# MainBoard_Schematic.net
KiCad netlist of a schematic drawn in Altium Designer
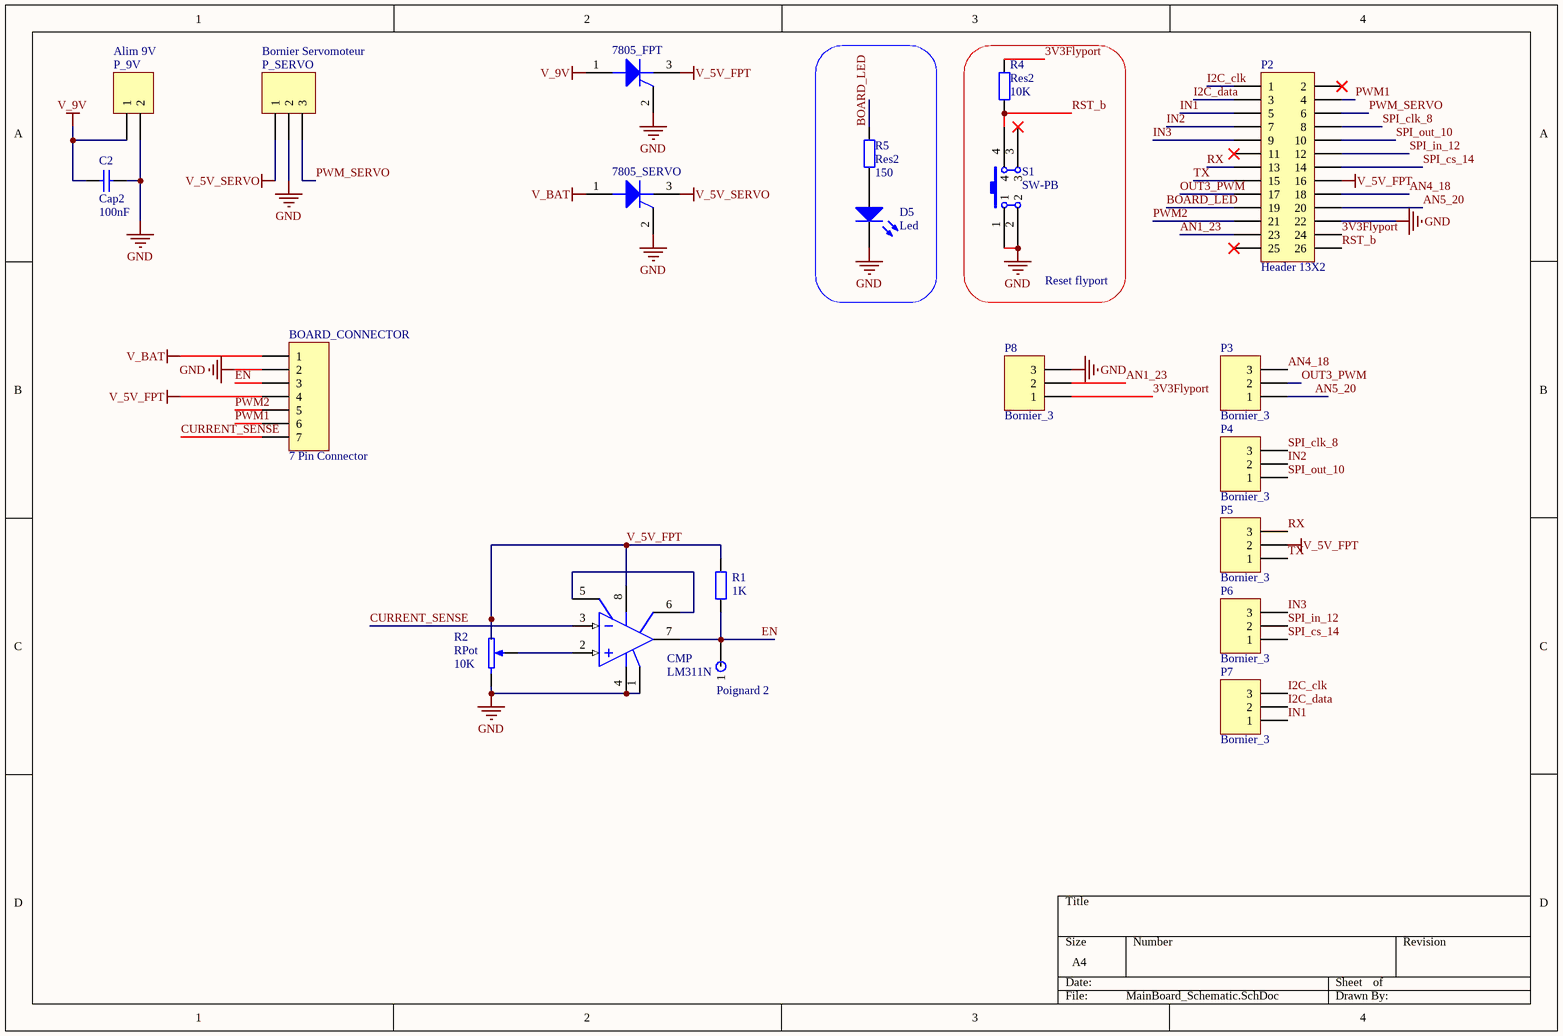
[diagram p0: MainBoard_Schematic.SchDoc]

(export (version "E")
  (design (tool "Eeschema 10.0.6"))
  (components
    (comp (ref "7805_FPT")
      (value "SCR")
      (footprint "TO-220-AB")
      (description "Silicon Controlled Rectifier")
      (fields (field (name "PUBLISHER") "Altium Limited"))
      (libsource (lib "Miscellaneous Devices") (part "SCR"))
    )
    (comp (ref "7805_SERVO")
      (value "SCR")
      (footprint "TO-220-AB")
      (description "Silicon Controlled Rectifier")
      (fields (field (name "PUBLISHER") "Altium Limited"))
      (libsource (lib "Miscellaneous Devices") (part "SCR"))
    )
    (comp (ref "BOARD_CONNECTOR")
      (value "7 Pin Connector")
      (footprint "HDR1X7")
      (description "Header, 7-Pin")
      (fields (field (name "PUBLISHER") "Altium Limited"))
      (libsource (lib "Miscellaneous Connectors") (part "Header 7"))
    )
    (comp (ref "C2")
      (value "Cap2")
      (footprint "CAPA2")
      (description "Capacitor")
      (fields (field (name "ALTIUM_VALUE") "100nF") (field (name "PUBLISHER") "Altium Limited"))
      (libsource (lib "LIBRAIRIE_INTEGREE_PHELMA1") (part "Cap2"))
    )
    (comp (ref "CMP")
      (value "LM311N")
      (footprint "LIBRAIRIE_INTEGREE_PHELMA1:DIP8")
      (description "Voltage Comparator")
      (fields (field (name "PUBLISHER") "Altium Limited"))
      (libsource (lib "LIBRAIRIE_INTEGREE_PHELMA1") (part "LM311N"))
    )
    (comp (ref "D5")
      (value "Led")
      (footprint "LED")
      (description "LED")
      (fields (field (name "PUBLISHER") "Altium Limited"))
      (libsource (lib "LIBRAIRIE_INTEGREE_PHELMA1") (part "Led"))
    )
    (comp (ref "P2")
      (value "Header 13X2")
      (footprint "HDR2X13")
      (description "Header, 13-Pin, Dual row")
      (fields (field (name "PUBLISHER") "Altium Limited"))
      (libsource (lib "Miscellaneous Connectors") (part "Header 13X2"))
    )
    (comp (ref "P3")
      (value "Bornier_3")
      (footprint "Bornier_3")
      (description "Header, 3-Pin")
      (fields (field (name "PUBLISHER") "Altium Limited"))
      (libsource (lib "") (part "Bornier_3_1"))
    )
    (comp (ref "P4")
      (value "Bornier_3")
      (footprint "Bornier_3")
      (description "Header, 3-Pin")
      (fields (field (name "PUBLISHER") "Altium Limited"))
      (libsource (lib "") (part "Bornier_3_1"))
    )
    (comp (ref "P5")
      (value "Bornier_3")
      (footprint "Bornier_3")
      (description "Header, 3-Pin")
      (fields (field (name "PUBLISHER") "Altium Limited"))
      (libsource (lib "") (part "Bornier_3_1"))
    )
    (comp (ref "P6")
      (value "Bornier_3")
      (footprint "Bornier_3")
      (description "Header, 3-Pin")
      (fields (field (name "PUBLISHER") "Altium Limited"))
      (libsource (lib "") (part "Bornier_3_1"))
    )
    (comp (ref "P7")
      (value "Bornier_3")
      (footprint "Bornier_3")
      (description "Header, 3-Pin")
      (fields (field (name "PUBLISHER") "Altium Limited"))
      (libsource (lib "") (part "Bornier_3_1"))
    )
    (comp (ref "P8")
      (value "Bornier_3")
      (footprint "Bornier_3")
      (description "Header, 3-Pin")
      (fields (field (name "PUBLISHER") "Altium Limited"))
      (libsource (lib "") (part "Bornier_3_1"))
    )
    (comp (ref "Poignard 2")
      (value "Poignard")
      (footprint "Poignard")
      (fields (field (name "PUBLISHER") "Altium Limited"))
      (libsource (lib "INTEGRATED_LIBRARY1_CONNECTEURS") (part "Poignard"))
    )
    (comp (ref "P_9V")
      (value "Alim 9V")
      (footprint "Bornier_2")
      (description "Header, 2-Pin")
      (fields (field (name "PUBLISHER") "Altium Limited"))
      (libsource (lib "INTEGRATED_LIBRARY1_CONNECTEURS") (part "Bornier_2"))
    )
    (comp (ref "P_SERVO")
      (value "Bornier Servomoteur")
      (footprint "Bornier_3")
      (description "Header, 3-Pin")
      (fields (field (name "PUBLISHER") "Altium Limited"))
      (libsource (lib "INTEGRATED_LIBRARY1_CONNECTEURS") (part "Bornier_3"))
    )
    (comp (ref "R1")
      (value "1K")
      (footprint "res5_1/4W")
      (description "Resistor")
      (fields (field (name "Comment") "Res2") (field (name "PUBLISHER") "Altium Limited"))
      (libsource (lib "") (part "Res2_1"))
    )
    (comp (ref "R2")
      (value "RPot")
      (footprint "AJUSTABLE")
      (description "Potentiometer")
      (fields (field (name "ALTIUM_VALUE") "10K") (field (name "PUBLISHER") "Altium Limited"))
      (libsource (lib "LIBRAIRIE_INTEGREE_PHELMA1") (part "RPot"))
    )
    (comp (ref "R4")
      (value "Res2")
      (footprint "res5_1/4W")
      (description "Resistor")
      (fields (field (name "ALTIUM_VALUE") "10K") (field (name "PUBLISHER") "Altium Limited"))
      (libsource (lib "LIBRAIRIE_INTEGREE_PHELMA1") (part "Res2"))
    )
    (comp (ref "R5")
      (value "Res2")
      (footprint "res5_1/4W")
      (description "Resistor")
      (fields (field (name "ALTIUM_VALUE") "150") (field (name "PUBLISHER") "Altium Limited"))
      (libsource (lib "LIBRAIRIE_INTEGREE_PHELMA1") (part "Res2"))
    )
    (comp (ref "S1")
      (value "SW-PB")
      (footprint "SW_BP")
      (description "Switch")
      (fields (field (name "PUBLISHER") "Altium Limited"))
      (libsource (lib "INTEGRATED_LIBRARY1_CONNECTEURS") (part "SW-PB"))
    )
  )
  (nets
    (net (code "1") (name "/3V3Flyport") (class "Default")
      (node (ref "P2") (pin "24") (pinfunction "24_24") (pintype "passive"))
      (node (ref "P8") (pin "1") (pinfunction "1_1") (pintype "passive"))
      (node (ref "R4") (pin "1") (pinfunction "1_1") (pintype "passive"))
    )
    (net (code "2") (name "/AN1_23") (class "Default")
      (node (ref "P2") (pin "23") (pinfunction "23_23") (pintype "passive"))
      (node (ref "P8") (pin "2") (pinfunction "2_2") (pintype "passive"))
    )
    (net (code "3") (name "/AN4_18") (class "Default")
      (node (ref "P2") (pin "18") (pinfunction "18_18") (pintype "passive"))
      (node (ref "P3") (pin "3") (pinfunction "3_3") (pintype "passive"))
    )
    (net (code "4") (name "/AN5_20") (class "Default")
      (node (ref "P2") (pin "20") (pinfunction "20_20") (pintype "passive"))
      (node (ref "P3") (pin "1") (pinfunction "1_1") (pintype "passive"))
    )
    (net (code "5") (name "/BOARD_LED") (class "Default")
      (node (ref "P2") (pin "19") (pinfunction "19_19") (pintype "passive"))
      (node (ref "R5") (pin "1") (pinfunction "1_1") (pintype "passive"))
    )
    (net (code "6") (name "/CURRENT_SENSE") (class "Default")
      (node (ref "BOARD_CONNECTOR") (pin "7") (pinfunction "7_7") (pintype "passive"))
      (node (ref "CMP") (pin "3") (pinfunction "IN-_3") (pintype "input"))
    )
    (net (code "7") (name "/EN") (class "Default")
      (node (ref "BOARD_CONNECTOR") (pin "3") (pinfunction "3_3") (pintype "passive"))
      (node (ref "CMP") (pin "7") (pinfunction "OUT_7") (pintype "open_collector"))
      (node (ref "Poignard 2") (pin "1") (pinfunction "1_1") (pintype "passive"))
      (node (ref "R1") (pin "1") (pinfunction "1_1") (pintype "passive"))
    )
    (net (code "8") (name "/I2C_clk") (class "Default")
      (node (ref "P2") (pin "1") (pinfunction "1_1") (pintype "passive"))
      (node (ref "P7") (pin "3") (pinfunction "3_3") (pintype "passive"))
    )
    (net (code "9") (name "/I2C_data") (class "Default")
      (node (ref "P2") (pin "3") (pinfunction "3_3") (pintype "passive"))
      (node (ref "P7") (pin "2") (pinfunction "2_2") (pintype "passive"))
    )
    (net (code "10") (name "/IN1") (class "Default")
      (node (ref "P2") (pin "5") (pinfunction "5_5") (pintype "passive"))
      (node (ref "P7") (pin "1") (pinfunction "1_1") (pintype "passive"))
    )
    (net (code "11") (name "/IN2") (class "Default")
      (node (ref "P2") (pin "7") (pinfunction "7_7") (pintype "passive"))
      (node (ref "P4") (pin "2") (pinfunction "2_2") (pintype "passive"))
    )
    (net (code "12") (name "/IN3") (class "Default")
      (node (ref "P2") (pin "9") (pinfunction "9_9") (pintype "passive"))
      (node (ref "P6") (pin "3") (pinfunction "3_3") (pintype "passive"))
    )
    (net (code "13") (name "/OUT3_PWM") (class "Default")
      (node (ref "P2") (pin "17") (pinfunction "17_17") (pintype "passive"))
      (node (ref "P3") (pin "2") (pinfunction "2_2") (pintype "passive"))
    )
    (net (code "14") (name "/PWM1") (class "Default")
      (node (ref "BOARD_CONNECTOR") (pin "6") (pinfunction "6_6") (pintype "passive"))
      (node (ref "P2") (pin "4") (pinfunction "4_4") (pintype "passive"))
    )
    (net (code "15") (name "/PWM2") (class "Default")
      (node (ref "BOARD_CONNECTOR") (pin "5") (pinfunction "5_5") (pintype "passive"))
      (node (ref "P2") (pin "21") (pinfunction "21_21") (pintype "passive"))
    )
    (net (code "16") (name "/PWM_SERVO") (class "Default")
      (node (ref "P2") (pin "6") (pinfunction "6_6") (pintype "passive"))
      (node (ref "P_SERVO") (pin "3") (pinfunction "3_3") (pintype "passive"))
    )
    (net (code "17") (name "/RST_b") (class "Default")
      (node (ref "P2") (pin "26") (pinfunction "26_26") (pintype "passive"))
      (node (ref "R4") (pin "2") (pinfunction "2_2") (pintype "passive"))
      (node (ref "S1") (pin "4") (pinfunction "4_4") (pintype "passive"))
    )
    (net (code "18") (name "/RX") (class "Default")
      (node (ref "P2") (pin "13") (pinfunction "13_13") (pintype "passive"))
      (node (ref "P5") (pin "3") (pinfunction "3_3") (pintype "passive"))
    )
    (net (code "19") (name "/SPI_clk_8") (class "Default")
      (node (ref "P2") (pin "8") (pinfunction "8_8") (pintype "passive"))
      (node (ref "P4") (pin "3") (pinfunction "3_3") (pintype "passive"))
    )
    (net (code "20") (name "/SPI_cs_14") (class "Default")
      (node (ref "P2") (pin "14") (pinfunction "14_14") (pintype "passive"))
      (node (ref "P6") (pin "1") (pinfunction "1_1") (pintype "passive"))
    )
    (net (code "21") (name "/SPI_in_12") (class "Default")
      (node (ref "P2") (pin "12") (pinfunction "12_12") (pintype "passive"))
      (node (ref "P6") (pin "2") (pinfunction "2_2") (pintype "passive"))
    )
    (net (code "22") (name "/SPI_out_10") (class "Default")
      (node (ref "P2") (pin "10") (pinfunction "10_10") (pintype "passive"))
      (node (ref "P4") (pin "1") (pinfunction "1_1") (pintype "passive"))
    )
    (net (code "23") (name "/TX") (class "Default")
      (node (ref "P2") (pin "15") (pinfunction "15_15") (pintype "passive"))
      (node (ref "P5") (pin "1") (pinfunction "1_1") (pintype "passive"))
    )
    (net (code "24") (name "GND") (class "Default")
      (node (ref "7805_FPT") (pin "2") (pinfunction "GND_2") (pintype "power_in"))
      (node (ref "7805_SERVO") (pin "2") (pinfunction "GND_2") (pintype "power_in"))
      (node (ref "BOARD_CONNECTOR") (pin "2") (pinfunction "2_2") (pintype "passive"))
      (node (ref "C2") (pin "2") (pinfunction "2_2") (pintype "passive"))
      (node (ref "CMP") (pin "1") (pinfunction "GND_1") (pintype "power_in"))
      (node (ref "CMP") (pin "4") (pinfunction "V-_(CASE)_4") (pintype "power_in"))
      (node (ref "D5") (pin "2") (pinfunction "K_2") (pintype "passive"))
      (node (ref "P2") (pin "22") (pinfunction "22_22") (pintype "passive"))
      (node (ref "P8") (pin "3") (pinfunction "3_3") (pintype "passive"))
      (node (ref "P_9V") (pin "2") (pinfunction "2_2") (pintype "passive"))
      (node (ref "P_SERVO") (pin "2") (pinfunction "2_2") (pintype "passive"))
      (node (ref "R2") (pin "3") (pinfunction "TOP_3") (pintype "passive"))
      (node (ref "S1") (pin "1") (pinfunction "1_1") (pintype "passive"))
      (node (ref "S1") (pin "2") (pinfunction "2_2") (pintype "passive"))
    )
    (net (code "25") (name "Net-(CMP-BAL)") (class "Default")
      (node (ref "CMP") (pin "5") (pinfunction "BAL_5") (pintype "passive"))
      (node (ref "CMP") (pin "6") (pinfunction "BAL/STB_6") (pintype "passive"))
    )
    (net (code "26") (name "Net-(CMP-IN+)") (class "Default")
      (node (ref "CMP") (pin "2") (pinfunction "IN+_2") (pintype "input"))
      (node (ref "R2") (pin "2") (pinfunction "TAP_2") (pintype "passive"))
    )
    (net (code "27") (name "Net-(D5-A)") (class "Default")
      (node (ref "D5") (pin "1") (pinfunction "A_1") (pintype "passive"))
      (node (ref "R5") (pin "2") (pinfunction "2_2") (pintype "passive"))
    )
    (net (code "28") (name "V_5V_FPT") (class "Default")
      (node (ref "7805_FPT") (pin "3") (pinfunction "OUT_3") (pintype "power_in"))
      (node (ref "BOARD_CONNECTOR") (pin "4") (pinfunction "4_4") (pintype "passive"))
      (node (ref "CMP") (pin "8") (pinfunction "V+_8") (pintype "power_in"))
      (node (ref "P2") (pin "16") (pinfunction "16_16") (pintype "passive"))
      (node (ref "P5") (pin "2") (pinfunction "2_2") (pintype "passive"))
      (node (ref "R1") (pin "2") (pinfunction "2_2") (pintype "passive"))
      (node (ref "R2") (pin "1") (pinfunction "BOT_1") (pintype "passive"))
    )
    (net (code "29") (name "V_5V_SERVO") (class "Default")
      (node (ref "7805_SERVO") (pin "3") (pinfunction "OUT_3") (pintype "power_in"))
      (node (ref "P_SERVO") (pin "1") (pinfunction "1_1") (pintype "passive"))
    )
    (net (code "30") (name "V_9V") (class "Default")
      (node (ref "7805_FPT") (pin "1") (pinfunction "IN_1") (pintype "power_in"))
      (node (ref "C2") (pin "1") (pinfunction "1_1") (pintype "passive"))
      (node (ref "P_9V") (pin "1") (pinfunction "1_1") (pintype "passive"))
    )
    (net (code "31") (name "V_BAT") (class "Default")
      (node (ref "7805_SERVO") (pin "1") (pinfunction "IN_1") (pintype "power_in"))
      (node (ref "BOARD_CONNECTOR") (pin "1") (pinfunction "1_1") (pintype "passive"))
    )
    (net (code "32") (name "unconnected-(P2-Pad2)") (class "Default")
      (node (ref "P2") (pin "2") (pinfunction "2_2") (pintype "passive+no_connect"))
    )
    (net (code "33") (name "unconnected-(P2-Pad11)") (class "Default")
      (node (ref "P2") (pin "11") (pinfunction "11_11") (pintype "passive+no_connect"))
    )
    (net (code "34") (name "unconnected-(P2-Pad25)") (class "Default")
      (node (ref "P2") (pin "25") (pinfunction "25_25") (pintype "passive+no_connect"))
    )
    (net (code "35") (name "unconnected-(S1-Pad3)") (class "Default")
      (node (ref "S1") (pin "3") (pinfunction "3_3") (pintype "passive+no_connect"))
    )
  )
)
